# 05_-_AUDIO.net
KiCad netlist of a schematic drawn in Altium Designer
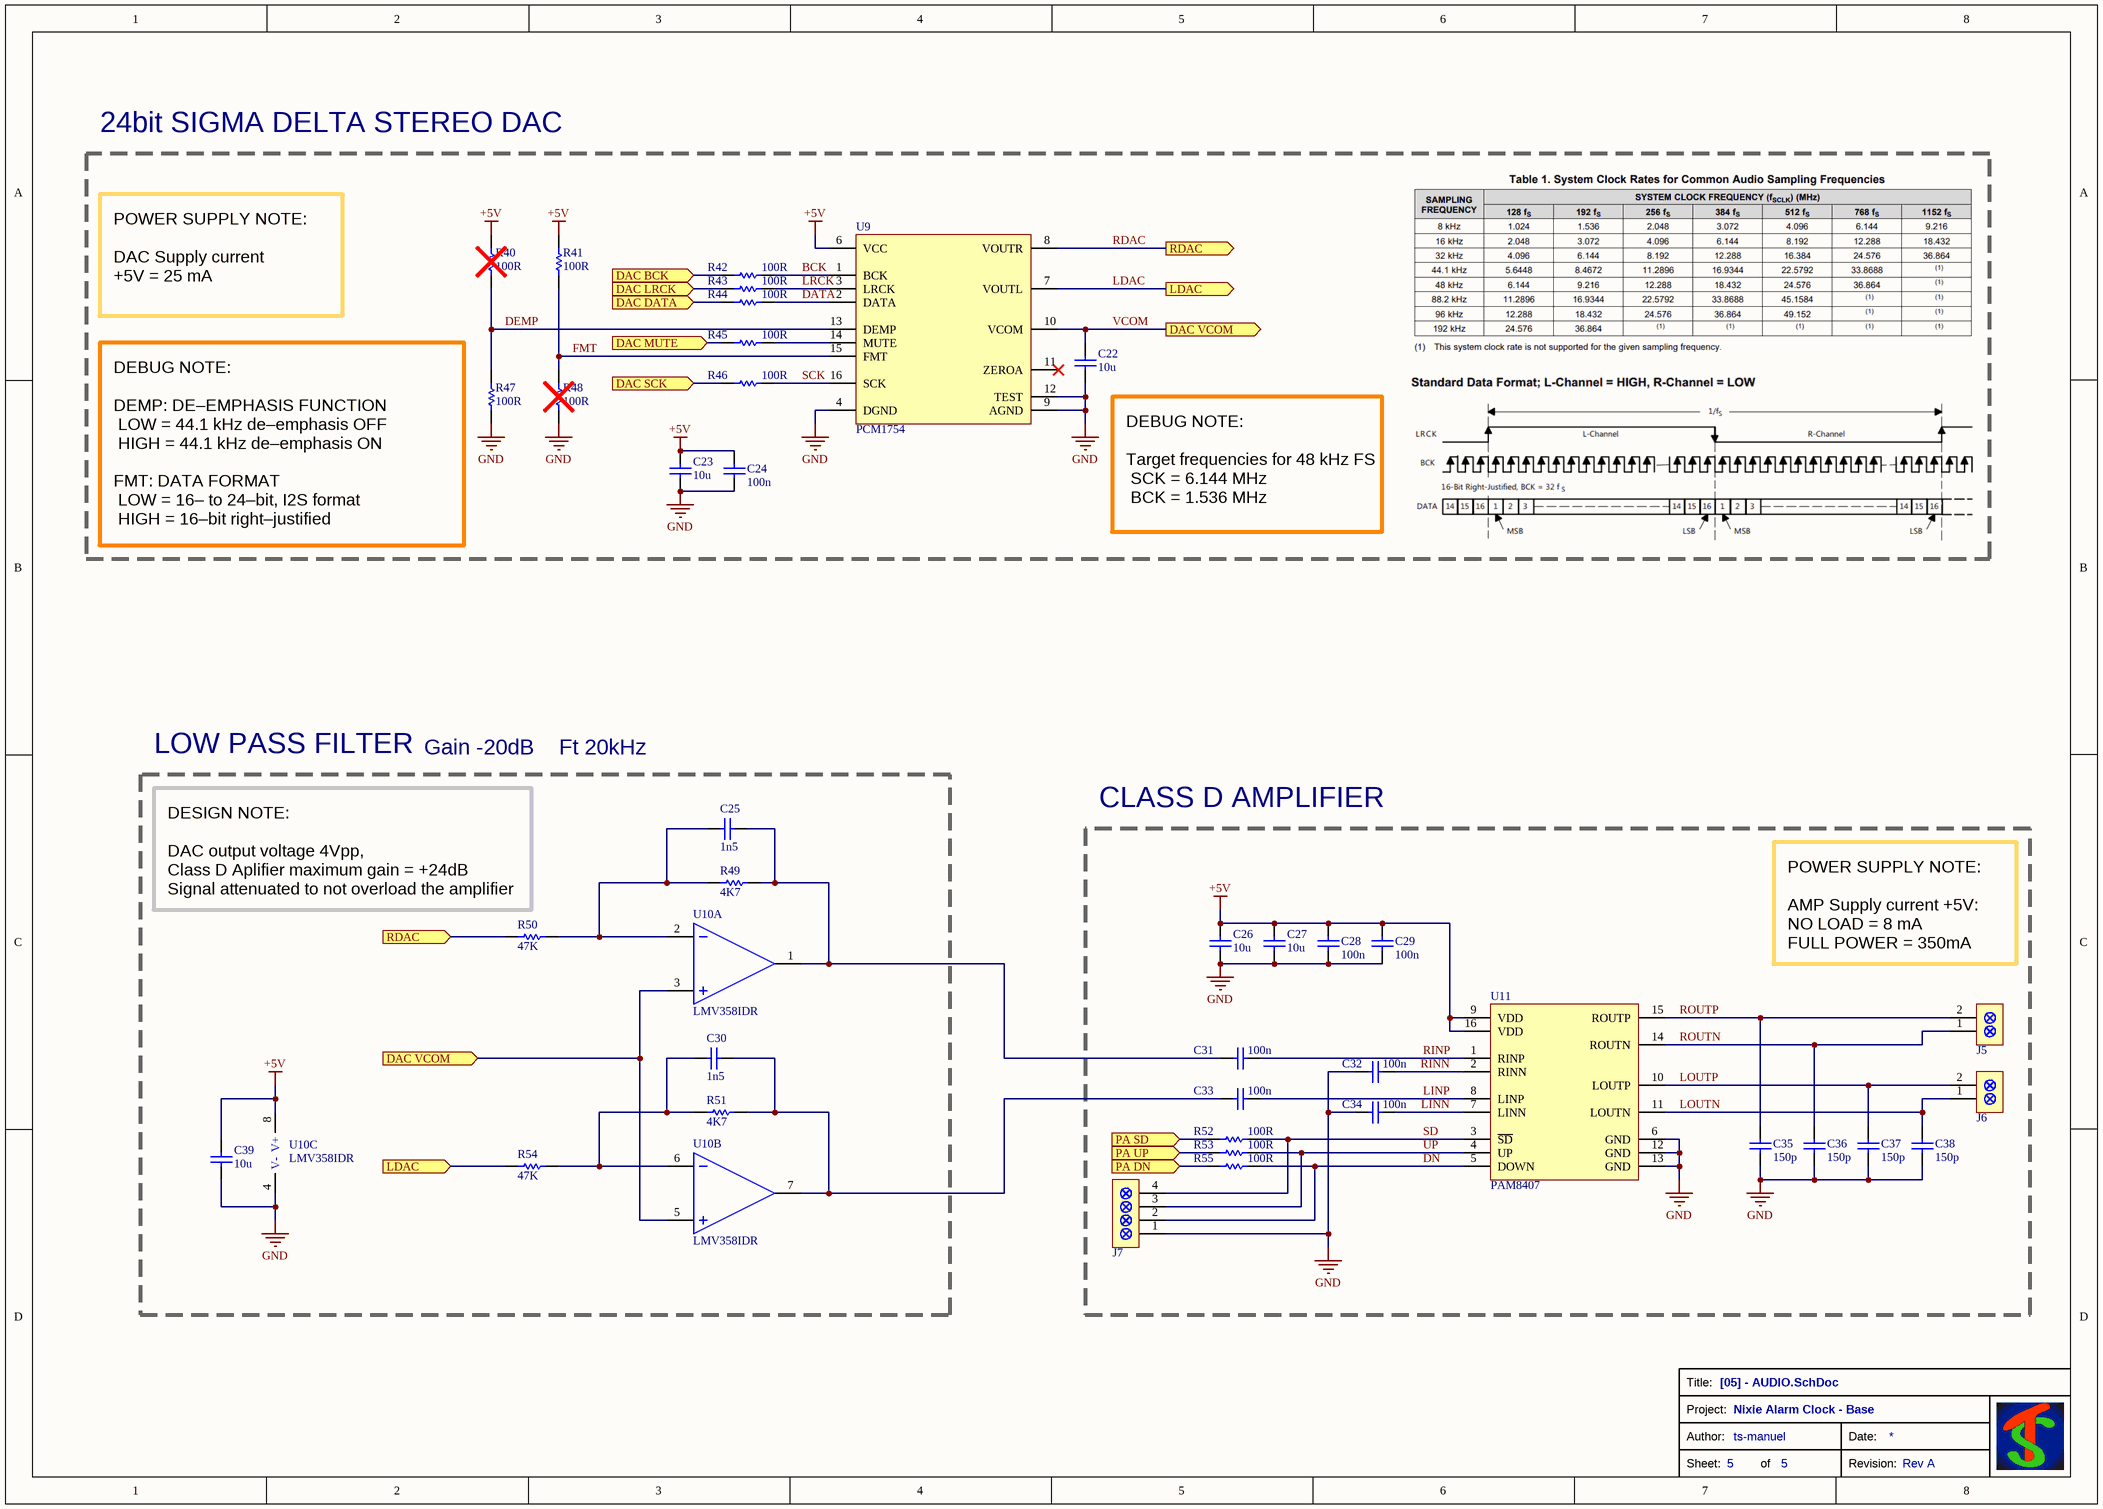
[diagram p0: [05] - AUDIO.SchDoc]

(export (version "E")
  (design (tool "Eeschema 10.0.6"))
  (components
    (comp (ref "C22")
      (value "10u")
      (footprint "CAP-0805")
      (description "MLCC - SMD 25V 10uF X5R 10%")
      (fields (field (name "MANUFACTURER") "Samsung") (field (name "TOLERANCE") "10%"))
      (libsource (lib "Passives") (part "CAP-0805-10u-25V-X5R-10%"))
    )
    (comp (ref "C23")
      (value "10u")
      (footprint "CAP-0805")
      (description "MLCC - SMD 25V 10uF X5R 10%")
      (fields (field (name "MANUFACTURER") "Samsung") (field (name "TOLERANCE") "10%"))
      (libsource (lib "Passives") (part "CAP-0805-10u-25V-X5R-10%"))
    )
    (comp (ref "C24")
      (value "100n")
      (footprint "CAP-0603")
      (description "MLCC - SMD 16V 100nF X7R 0603 20%")
      (fields (field (name "TOLERANCE") "20%") (field (name "MANUFACTURER") "KEMET"))
      (libsource (lib "Passives") (part "CAP-0603-100n-16V-X7R-20%"))
    )
    (comp (ref "C25")
      (value "1n5")
      (footprint "CAP-0603")
      (description "MLCC - SMD 50V 1.5nF NP0 0603 5%")
      (fields (field (name "MANUFACTURER") "Murata") (field (name "TOLERANCE") "5%"))
      (libsource (lib "Passives") (part "CAP-0603-1n5-50V-NP0-5%"))
    )
    (comp (ref "C26")
      (value "10u")
      (footprint "CAP-0805")
      (description "MLCC - SMD 25V 10uF X5R 10%")
      (fields (field (name "MANUFACTURER") "Samsung") (field (name "TOLERANCE") "10%"))
      (libsource (lib "Passives") (part "CAP-0805-10u-25V-X5R-10%"))
    )
    (comp (ref "C27")
      (value "10u")
      (footprint "CAP-0805")
      (description "MLCC - SMD 25V 10uF X5R 10%")
      (fields (field (name "MANUFACTURER") "Samsung") (field (name "TOLERANCE") "10%"))
      (libsource (lib "Passives") (part "CAP-0805-10u-25V-X5R-10%"))
    )
    (comp (ref "C28")
      (value "100n")
      (footprint "CAP-0603")
      (description "MLCC - SMD 16V 100nF X7R 0603 20%")
      (fields (field (name "TOLERANCE") "20%") (field (name "MANUFACTURER") "KEMET"))
      (libsource (lib "Passives") (part "CAP-0603-100n-16V-X7R-20%"))
    )
    (comp (ref "C29")
      (value "100n")
      (footprint "CAP-0603")
      (description "MLCC - SMD 16V 100nF X7R 0603 20%")
      (fields (field (name "TOLERANCE") "20%") (field (name "MANUFACTURER") "KEMET"))
      (libsource (lib "Passives") (part "CAP-0603-100n-16V-X7R-20%"))
    )
    (comp (ref "C30")
      (value "1n5")
      (footprint "CAP-0603")
      (description "MLCC - SMD 50V 1.5nF NP0 0603 5%")
      (fields (field (name "MANUFACTURER") "Murata") (field (name "TOLERANCE") "5%"))
      (libsource (lib "Passives") (part "CAP-0603-1n5-50V-NP0-5%"))
    )
    (comp (ref "C31")
      (value "100n")
      (footprint "CAP-0603")
      (description "MLCC - SMD 16V 100nF X7R 0603 20%")
      (fields (field (name "TOLERANCE") "20%") (field (name "MANUFACTURER") "KEMET"))
      (libsource (lib "Passives") (part "CAP-0603-100n-16V-X7R-20%"))
    )
    (comp (ref "C32")
      (value "100n")
      (footprint "CAP-0603")
      (description "MLCC - SMD 16V 100nF X7R 0603 20%")
      (fields (field (name "TOLERANCE") "20%") (field (name "MANUFACTURER") "KEMET"))
      (libsource (lib "Passives") (part "CAP-0603-100n-16V-X7R-20%"))
    )
    (comp (ref "C33")
      (value "100n")
      (footprint "CAP-0603")
      (description "MLCC - SMD 16V 100nF X7R 0603 20%")
      (fields (field (name "TOLERANCE") "20%") (field (name "MANUFACTURER") "KEMET"))
      (libsource (lib "Passives") (part "CAP-0603-100n-16V-X7R-20%"))
    )
    (comp (ref "C34")
      (value "100n")
      (footprint "CAP-0603")
      (description "MLCC - SMD 16V 100nF X7R 0603 20%")
      (fields (field (name "TOLERANCE") "20%") (field (name "MANUFACTURER") "KEMET"))
      (libsource (lib "Passives") (part "CAP-0603-100n-16V-X7R-20%"))
    )
    (comp (ref "C35")
      (value "150p")
      (footprint "CAP-0805")
      (description "MLCC - SMD 100V 150pF NP0 0805 5%")
      (fields (field (name "MANUFACTURER") "Wurth Electronics") (field (name "Comment") "885012007083"))
      (libsource (lib "Passives") (part "CAP-0805-150p-100V-NP0-5%"))
    )
    (comp (ref "C36")
      (value "150p")
      (footprint "CAP-0805")
      (description "MLCC - SMD 100V 150pF NP0 0805 5%")
      (fields (field (name "MANUFACTURER") "Wurth Electronics") (field (name "Comment") "885012007083"))
      (libsource (lib "Passives") (part "CAP-0805-150p-100V-NP0-5%"))
    )
    (comp (ref "C37")
      (value "150p")
      (footprint "CAP-0805")
      (description "MLCC - SMD 100V 150pF NP0 0805 5%")
      (fields (field (name "MANUFACTURER") "Wurth Electronics") (field (name "Comment") "885012007083"))
      (libsource (lib "Passives") (part "CAP-0805-150p-100V-NP0-5%"))
    )
    (comp (ref "C38")
      (value "150p")
      (footprint "CAP-0805")
      (description "MLCC - SMD 100V 150pF NP0 0805 5%")
      (fields (field (name "MANUFACTURER") "Wurth Electronics") (field (name "Comment") "885012007083"))
      (libsource (lib "Passives") (part "CAP-0805-150p-100V-NP0-5%"))
    )
    (comp (ref "C39")
      (value "10u")
      (footprint "CAP-0805")
      (description "MLCC - SMD 25V 10uF X5R 10%")
      (fields (field (name "MANUFACTURER") "Samsung") (field (name "TOLERANCE") "10%"))
      (libsource (lib "Passives") (part "CAP-0805-10u-25V-X5R-10%"))
    )
    (comp (ref "J5")
      (value "SCREW-TH-BLOCK-200-2")
      (footprint "SCREW-TH-BLOCK-200-2")
      (description "Screw Therminal Block 200 mil Pitch 2 Contacts")
      (libsource (lib "mt_local_library") (part "SCREW-TH-BLOCK-200-2"))
    )
    (comp (ref "J6")
      (value "SCREW-TH-BLOCK-200-2")
      (footprint "SCREW-TH-BLOCK-200-2")
      (description "Screw Therminal Block 200 mil Pitch 2 Contacts")
      (libsource (lib "mt_local_library") (part "SCREW-TH-BLOCK-200-2"))
    )
    (comp (ref "J7")
      (value "SCREW-TH-BLOCK-200-4")
      (footprint "SCREW-TH-BLOCK-200-4")
      (description "Screw Therminal Block 200 mil Pitch 4 Contacts")
      (libsource (lib "mt_local_library") (part "SCREW-TH-BLOCK-200-4"))
    )
    (comp (ref "R40")
      (value "100R")
      (footprint "RES-0603")
      (description "Thick Film - SMD 75V 1/10W 100 ohm 0603 1%")
      (fields (field (name "MANUFACTURER") "Yageo") (field (name "TOLERANCE") "1%"))
      (libsource (lib "Passives") (part "RES-0603-100R-1/10W-1%"))
    )
    (comp (ref "R41")
      (value "100R")
      (footprint "RES-0603")
      (description "Thick Film - SMD 75V 1/10W 100 ohm 0603 1%")
      (fields (field (name "MANUFACTURER") "Yageo") (field (name "TOLERANCE") "1%"))
      (libsource (lib "Passives") (part "RES-0603-100R-1/10W-1%"))
    )
    (comp (ref "R42")
      (value "100R")
      (footprint "RES-0603")
      (description "Thick Film - SMD 75V 1/10W 100 ohm 0603 1%")
      (fields (field (name "MANUFACTURER") "Yageo") (field (name "TOLERANCE") "1%"))
      (libsource (lib "Passives") (part "RES-0603-100R-1/10W-1%"))
    )
    (comp (ref "R43")
      (value "100R")
      (footprint "RES-0603")
      (description "Thick Film - SMD 75V 1/10W 100 ohm 0603 1%")
      (fields (field (name "MANUFACTURER") "Yageo") (field (name "TOLERANCE") "1%"))
      (libsource (lib "Passives") (part "RES-0603-100R-1/10W-1%"))
    )
    (comp (ref "R44")
      (value "100R")
      (footprint "RES-0603")
      (description "Thick Film - SMD 75V 1/10W 100 ohm 0603 1%")
      (fields (field (name "MANUFACTURER") "Yageo") (field (name "TOLERANCE") "1%"))
      (libsource (lib "Passives") (part "RES-0603-100R-1/10W-1%"))
    )
    (comp (ref "R45")
      (value "100R")
      (footprint "RES-0603")
      (description "Thick Film - SMD 75V 1/10W 100 ohm 0603 1%")
      (fields (field (name "MANUFACTURER") "Yageo") (field (name "TOLERANCE") "1%"))
      (libsource (lib "Passives") (part "RES-0603-100R-1/10W-1%"))
    )
    (comp (ref "R46")
      (value "100R")
      (footprint "RES-0603")
      (description "Thick Film - SMD 75V 1/10W 100 ohm 0603 1%")
      (fields (field (name "MANUFACTURER") "Yageo") (field (name "TOLERANCE") "1%"))
      (libsource (lib "Passives") (part "RES-0603-100R-1/10W-1%"))
    )
    (comp (ref "R47")
      (value "100R")
      (footprint "RES-0603")
      (description "Thick Film - SMD 75V 1/10W 100 ohm 0603 1%")
      (fields (field (name "MANUFACTURER") "Yageo") (field (name "TOLERANCE") "1%"))
      (libsource (lib "Passives") (part "RES-0603-100R-1/10W-1%"))
    )
    (comp (ref "R48")
      (value "100R")
      (footprint "RES-0603")
      (description "Thick Film - SMD 75V 1/10W 100 ohm 0603 1%")
      (fields (field (name "MANUFACTURER") "Yageo") (field (name "TOLERANCE") "1%"))
      (libsource (lib "Passives") (part "RES-0603-100R-1/10W-1%"))
    )
    (comp (ref "R49")
      (value "4K7")
      (footprint "RES-0603")
      (description "Thick Film - SMD 75V 1/10W 4.7K ohm 0603 1%")
      (fields (field (name "MANUFACTURER") "Yageo") (field (name "TOLERANCE") "1%"))
      (libsource (lib "Passives") (part "RES-0603-4K7-1/10W-1%"))
    )
    (comp (ref "R50")
      (value "47K")
      (footprint "RES-0603")
      (description "Thick Film - SMD 75V 1/10W 47K ohm 0603 1%")
      (fields (field (name "MANUFACTURER") "Yageo") (field (name "TOLERANCE") "1%"))
      (libsource (lib "Passives") (part "RES-0603-47K-1/10W-1%"))
    )
    (comp (ref "R51")
      (value "4K7")
      (footprint "RES-0603")
      (description "Thick Film - SMD 75V 1/10W 4.7K ohm 0603 1%")
      (fields (field (name "MANUFACTURER") "Yageo") (field (name "TOLERANCE") "1%"))
      (libsource (lib "Passives") (part "RES-0603-4K7-1/10W-1%"))
    )
    (comp (ref "R52")
      (value "100R")
      (footprint "RES-0603")
      (description "Thick Film - SMD 75V 1/10W 100 ohm 0603 1%")
      (fields (field (name "MANUFACTURER") "Yageo") (field (name "TOLERANCE") "1%"))
      (libsource (lib "Passives") (part "RES-0603-100R-1/10W-1%"))
    )
    (comp (ref "R53")
      (value "100R")
      (footprint "RES-0603")
      (description "Thick Film - SMD 75V 1/10W 100 ohm 0603 1%")
      (fields (field (name "MANUFACTURER") "Yageo") (field (name "TOLERANCE") "1%"))
      (libsource (lib "Passives") (part "RES-0603-100R-1/10W-1%"))
    )
    (comp (ref "R54")
      (value "47K")
      (footprint "RES-0603")
      (description "Thick Film - SMD 75V 1/10W 47K ohm 0603 1%")
      (fields (field (name "MANUFACTURER") "Yageo") (field (name "TOLERANCE") "1%"))
      (libsource (lib "Passives") (part "RES-0603-47K-1/10W-1%"))
    )
    (comp (ref "R55")
      (value "100R")
      (footprint "RES-0603")
      (description "Thick Film - SMD 75V 1/10W 100 ohm 0603 1%")
      (fields (field (name "MANUFACTURER") "Yageo") (field (name "TOLERANCE") "1%"))
      (libsource (lib "Passives") (part "RES-0603-100R-1/10W-1%"))
    )
    (comp (ref "U9")
      (value "PCM1754")
      (footprint "SOP64P600X175-16N")
      (description "Circuiti integrati convertitori D/A audio 24-Bit 192kHz Stereo Audio DAC")
      (libsource (lib "mt_local_library") (part "DAC-STEREO-24bit-PCM1754"))
    )
    (comp (ref "U10")
      (value "LMV358IDR")
      (footprint "SOIC127P600X175-8N")
      (description "Low-Voltage Rail-to-Rail Output FET Input Dual Operational Amplifier")
      (fields (field (name "MANUFACTURER") "Texas Instruments"))
      (libsource (lib "mt_local_library") (part "OPAMP-FET-LMV358IDR-TI"))
    )
    (comp (ref "U11")
      (value "PAM8407")
      (footprint "SOIC127P600X175-16N")
      (description "2x3W Stereo Differential Input Class D Audio Amplifier\r\nwith Up/Down Volume Control")
      (libsource (lib "mt_local_library") (part "PAM8407"))
    )
  )
  (nets
    (net (code "1") (name "+5V") (class "Default")
      (node (ref "C23") (pin "1") (pinfunction "1_1") (pintype "passive"))
      (node (ref "C24") (pin "2") (pinfunction "2_2") (pintype "passive"))
      (node (ref "C26") (pin "1") (pinfunction "1_1") (pintype "passive"))
      (node (ref "C27") (pin "1") (pinfunction "1_1") (pintype "passive"))
      (node (ref "C28") (pin "2") (pinfunction "2_2") (pintype "passive"))
      (node (ref "C29") (pin "2") (pinfunction "2_2") (pintype "passive"))
      (node (ref "C39") (pin "1") (pinfunction "1_1") (pintype "passive"))
      (node (ref "R40") (pin "2") (pinfunction "2_2") (pintype "passive"))
      (node (ref "R41") (pin "2") (pinfunction "2_2") (pintype "passive"))
      (node (ref "U10") (pin "8") (pinfunction "V+_8") (pintype "power_in"))
      (node (ref "U11") (pin "16") (pinfunction "VDD_16") (pintype "power_in"))
      (node (ref "U11") (pin "9") (pinfunction "VDD_9") (pintype "power_in"))
      (node (ref "U9") (pin "6") (pinfunction "VCC_6") (pintype "power_in"))
    )
    (net (code "2") (name "/BCK") (class "Default")
      (node (ref "R42") (pin "2") (pinfunction "2_2") (pintype "passive"))
      (node (ref "U9") (pin "1") (pinfunction "BCK_1") (pintype "passive"))
    )
    (net (code "3") (name "/DAC BCK") (class "Default")
      (node (ref "R42") (pin "1") (pinfunction "1_1") (pintype "passive"))
    )
    (net (code "4") (name "/DAC DATA") (class "Default")
      (node (ref "R44") (pin "1") (pinfunction "1_1") (pintype "passive"))
    )
    (net (code "5") (name "/DAC LRCK") (class "Default")
      (node (ref "R43") (pin "1") (pinfunction "1_1") (pintype "passive"))
    )
    (net (code "6") (name "/DAC MUTE") (class "Default")
      (node (ref "R45") (pin "1") (pinfunction "1_1") (pintype "passive"))
    )
    (net (code "7") (name "/DAC SCK") (class "Default")
      (node (ref "R46") (pin "1") (pinfunction "1_1") (pintype "passive"))
    )
    (net (code "8") (name "/DATA") (class "Default")
      (node (ref "R44") (pin "2") (pinfunction "2_2") (pintype "passive"))
      (node (ref "U9") (pin "2") (pinfunction "DATA_2") (pintype "passive"))
    )
    (net (code "9") (name "/DEMP") (class "Default")
      (node (ref "R40") (pin "1") (pinfunction "1_1") (pintype "passive"))
      (node (ref "R47") (pin "2") (pinfunction "2_2") (pintype "passive"))
      (node (ref "U9") (pin "13") (pinfunction "DEMP_13") (pintype "passive"))
    )
    (net (code "10") (name "/DN") (class "Default")
      (node (ref "J7") (pin "2") (pinfunction "2_2") (pintype "passive"))
      (node (ref "R55") (pin "2") (pinfunction "2_2") (pintype "passive"))
      (node (ref "U11") (pin "5") (pinfunction "DOWN_5") (pintype "passive"))
    )
    (net (code "11") (name "/FMT") (class "Default")
      (node (ref "R41") (pin "1") (pinfunction "1_1") (pintype "passive"))
      (node (ref "R48") (pin "2") (pinfunction "2_2") (pintype "passive"))
      (node (ref "U9") (pin "15") (pinfunction "FMT_15") (pintype "passive"))
    )
    (net (code "12") (name "/LDAC") (class "Default")
      (node (ref "R54") (pin "2") (pinfunction "2_2") (pintype "passive"))
      (node (ref "U9") (pin "7") (pinfunction "VOUTL_7") (pintype "passive"))
    )
    (net (code "13") (name "/LINN") (class "Default")
      (node (ref "C34") (pin "2") (pinfunction "2_2") (pintype "passive"))
      (node (ref "U11") (pin "7") (pinfunction "LINN_7") (pintype "passive"))
    )
    (net (code "14") (name "/LINP") (class "Default")
      (node (ref "C33") (pin "2") (pinfunction "2_2") (pintype "passive"))
      (node (ref "U11") (pin "8") (pinfunction "LINP_8") (pintype "passive"))
    )
    (net (code "15") (name "/LOUTN") (class "Default")
      (node (ref "C38") (pin "2") (pinfunction "2_2") (pintype "passive"))
      (node (ref "J6") (pin "1") (pinfunction "1_1") (pintype "passive"))
      (node (ref "U11") (pin "11") (pinfunction "LOUTN_11") (pintype "passive"))
    )
    (net (code "16") (name "/LOUTP") (class "Default")
      (node (ref "C37") (pin "2") (pinfunction "2_2") (pintype "passive"))
      (node (ref "J6") (pin "2") (pinfunction "2_2") (pintype "passive"))
      (node (ref "U11") (pin "10") (pinfunction "LOUTP_10") (pintype "passive"))
    )
    (net (code "17") (name "/LRCK") (class "Default")
      (node (ref "R43") (pin "2") (pinfunction "2_2") (pintype "passive"))
      (node (ref "U9") (pin "3") (pinfunction "LRCK_3") (pintype "passive"))
    )
    (net (code "18") (name "/PA DN") (class "Default")
      (node (ref "R55") (pin "1") (pinfunction "1_1") (pintype "passive"))
    )
    (net (code "19") (name "/PA SD") (class "Default")
      (node (ref "R52") (pin "1") (pinfunction "1_1") (pintype "passive"))
    )
    (net (code "20") (name "/PA UP") (class "Default")
      (node (ref "R53") (pin "1") (pinfunction "1_1") (pintype "passive"))
    )
    (net (code "21") (name "/RDAC") (class "Default")
      (node (ref "R50") (pin "2") (pinfunction "2_2") (pintype "passive"))
      (node (ref "U9") (pin "8") (pinfunction "VOUTR_8") (pintype "passive"))
    )
    (net (code "22") (name "/RINN") (class "Default")
      (node (ref "C32") (pin "2") (pinfunction "2_2") (pintype "passive"))
      (node (ref "U11") (pin "2") (pinfunction "RINN_2") (pintype "passive"))
    )
    (net (code "23") (name "/RINP") (class "Default")
      (node (ref "C31") (pin "2") (pinfunction "2_2") (pintype "passive"))
      (node (ref "U11") (pin "1") (pinfunction "RINP_1") (pintype "passive"))
    )
    (net (code "24") (name "/ROUTN") (class "Default")
      (node (ref "C36") (pin "2") (pinfunction "2_2") (pintype "passive"))
      (node (ref "J5") (pin "1") (pinfunction "1_1") (pintype "passive"))
      (node (ref "U11") (pin "14") (pinfunction "ROUTN_14") (pintype "passive"))
    )
    (net (code "25") (name "/ROUTP") (class "Default")
      (node (ref "C35") (pin "2") (pinfunction "2_2") (pintype "passive"))
      (node (ref "J5") (pin "2") (pinfunction "2_2") (pintype "passive"))
      (node (ref "U11") (pin "15") (pinfunction "ROUTP_15") (pintype "passive"))
    )
    (net (code "26") (name "/SCK") (class "Default")
      (node (ref "R46") (pin "2") (pinfunction "2_2") (pintype "passive"))
      (node (ref "U9") (pin "16") (pinfunction "SCK_16") (pintype "passive"))
    )
    (net (code "27") (name "/SD") (class "Default")
      (node (ref "J7") (pin "4") (pinfunction "4_4") (pintype "passive"))
      (node (ref "R52") (pin "2") (pinfunction "2_2") (pintype "passive"))
      (node (ref "U11") (pin "3") (pinfunction "~{SD}_3") (pintype "passive"))
    )
    (net (code "28") (name "/UP") (class "Default")
      (node (ref "J7") (pin "3") (pinfunction "3_3") (pintype "passive"))
      (node (ref "R53") (pin "2") (pinfunction "2_2") (pintype "passive"))
      (node (ref "U11") (pin "4") (pinfunction "UP_4") (pintype "passive"))
    )
    (net (code "29") (name "/VCOM") (class "Default")
      (node (ref "C22") (pin "1") (pinfunction "1_1") (pintype "passive"))
      (node (ref "U10") (pin "3") (pinfunction "1IN+_3") (pintype "passive"))
      (node (ref "U10") (pin "5") (pinfunction "2IN+_5") (pintype "passive"))
      (node (ref "U9") (pin "10") (pinfunction "VCOM_10") (pintype "passive"))
    )
    (net (code "30") (name "GND") (class "Default")
      (node (ref "C22") (pin "2") (pinfunction "2_2") (pintype "passive"))
      (node (ref "C23") (pin "2") (pinfunction "2_2") (pintype "passive"))
      (node (ref "C24") (pin "1") (pinfunction "1_1") (pintype "passive"))
      (node (ref "C26") (pin "2") (pinfunction "2_2") (pintype "passive"))
      (node (ref "C27") (pin "2") (pinfunction "2_2") (pintype "passive"))
      (node (ref "C28") (pin "1") (pinfunction "1_1") (pintype "passive"))
      (node (ref "C29") (pin "1") (pinfunction "1_1") (pintype "passive"))
      (node (ref "C32") (pin "1") (pinfunction "1_1") (pintype "passive"))
      (node (ref "C34") (pin "1") (pinfunction "1_1") (pintype "passive"))
      (node (ref "C35") (pin "1") (pinfunction "1_1") (pintype "passive"))
      (node (ref "C36") (pin "1") (pinfunction "1_1") (pintype "passive"))
      (node (ref "C37") (pin "1") (pinfunction "1_1") (pintype "passive"))
      (node (ref "C38") (pin "1") (pinfunction "1_1") (pintype "passive"))
      (node (ref "C39") (pin "2") (pinfunction "2_2") (pintype "passive"))
      (node (ref "J7") (pin "1") (pinfunction "1_1") (pintype "passive"))
      (node (ref "R47") (pin "1") (pinfunction "1_1") (pintype "passive"))
      (node (ref "R48") (pin "1") (pinfunction "1_1") (pintype "passive"))
      (node (ref "U10") (pin "4") (pinfunction "V-_4") (pintype "power_in"))
      (node (ref "U11") (pin "12") (pinfunction "GND_12") (pintype "power_in"))
      (node (ref "U11") (pin "13") (pinfunction "GND_13") (pintype "power_in"))
      (node (ref "U11") (pin "6") (pinfunction "GND_6") (pintype "power_in"))
      (node (ref "U9") (pin "12") (pinfunction "TEST_12") (pintype "passive"))
      (node (ref "U9") (pin "4") (pinfunction "DGND_4") (pintype "power_in"))
      (node (ref "U9") (pin "9") (pinfunction "AGND_9") (pintype "power_in"))
    )
    (net (code "31") (name "Net-(U9-MUTE)") (class "Default")
      (node (ref "R45") (pin "2") (pinfunction "2_2") (pintype "passive"))
      (node (ref "U9") (pin "14") (pinfunction "MUTE_14") (pintype "passive"))
    )
    (net (code "32") (name "Net-(U10A-1IN-)") (class "Default")
      (node (ref "C25") (pin "1") (pinfunction "1_1") (pintype "passive"))
      (node (ref "R49") (pin "1") (pinfunction "1_1") (pintype "passive"))
      (node (ref "R50") (pin "1") (pinfunction "1_1") (pintype "passive"))
      (node (ref "U10") (pin "2") (pinfunction "1IN-_2") (pintype "passive"))
    )
    (net (code "33") (name "Net-(U10A-1OUT)") (class "Default")
      (node (ref "C25") (pin "2") (pinfunction "2_2") (pintype "passive"))
      (node (ref "C31") (pin "1") (pinfunction "1_1") (pintype "passive"))
      (node (ref "R49") (pin "2") (pinfunction "2_2") (pintype "passive"))
      (node (ref "U10") (pin "1") (pinfunction "1OUT_1") (pintype "passive"))
    )
    (net (code "34") (name "Net-(U10B-2IN-)") (class "Default")
      (node (ref "C30") (pin "1") (pinfunction "1_1") (pintype "passive"))
      (node (ref "R51") (pin "1") (pinfunction "1_1") (pintype "passive"))
      (node (ref "R54") (pin "1") (pinfunction "1_1") (pintype "passive"))
      (node (ref "U10") (pin "6") (pinfunction "2IN-_6") (pintype "passive"))
    )
    (net (code "35") (name "Net-(U10B-2OUT)") (class "Default")
      (node (ref "C30") (pin "2") (pinfunction "2_2") (pintype "passive"))
      (node (ref "C33") (pin "1") (pinfunction "1_1") (pintype "passive"))
      (node (ref "R51") (pin "2") (pinfunction "2_2") (pintype "passive"))
      (node (ref "U10") (pin "7") (pinfunction "2OUT_7") (pintype "passive"))
    )
    (net (code "36") (name "unconnected-(U9-ZEROA-Pad11)") (class "Default")
      (node (ref "U9") (pin "11") (pinfunction "ZEROA_11") (pintype "passive+no_connect"))
    )
  )
)
